# MusicalWheelchair.net
KiCad netlist of a schematic drawn in EAGLE
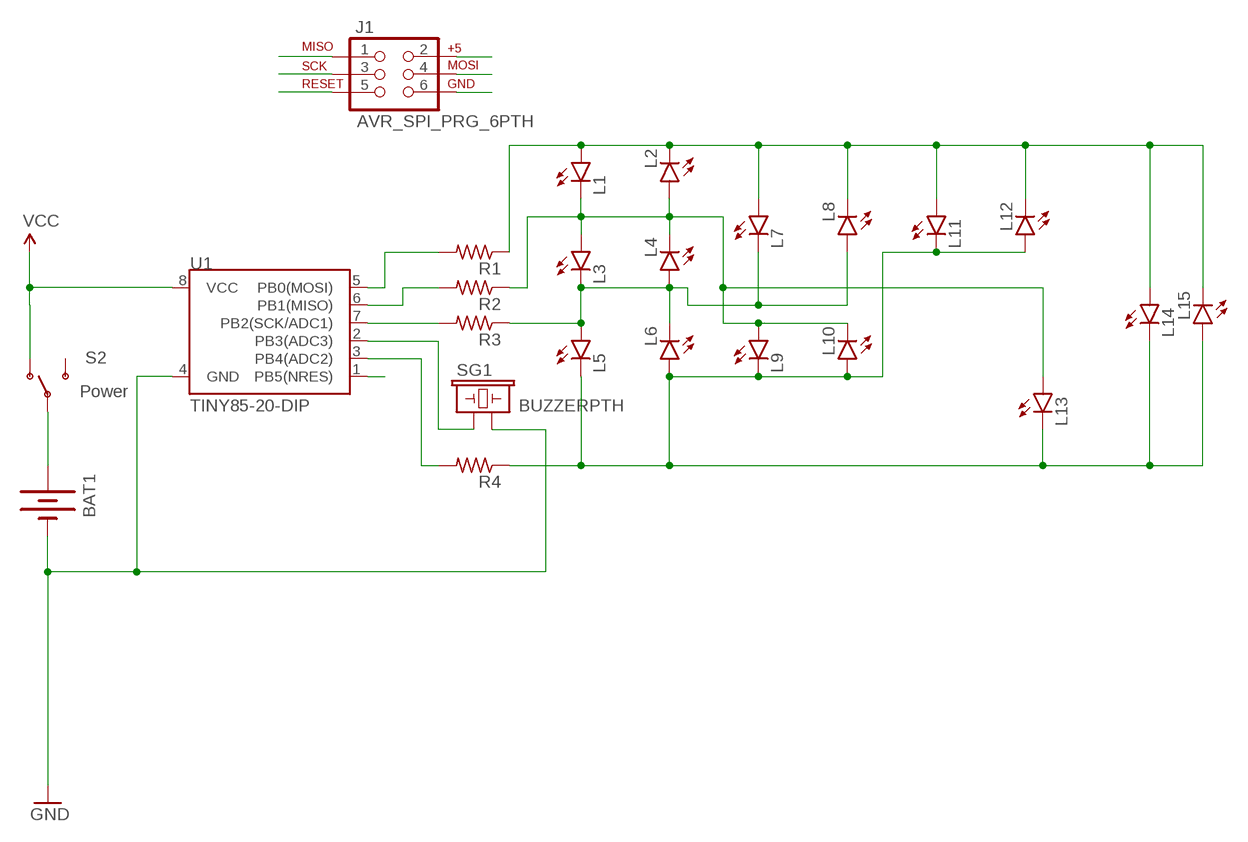
[diagram p0: schematic, sheet 1]

(export (version "E")
  (design (tool "Eeschema 10.0.6"))
  (components
    (comp (ref "BAT1")
      (value "BATTERY20PTH")
      (footprint "eagle-import:BATTCOM_20MM_PTH")
      (libsource (lib "eagle-import") (part "BATTERY20PTH"))
    )
    (comp (ref "J1")
      (value "AVR_SPI_PRG_6PTH")
      (footprint "eagle-import:2X3")
      (libsource (lib "eagle-import") (part "AVR_SPI_PRG_6PTH"))
    )
    (comp (ref "L1")
      (value "LED5MM")
      (footprint "eagle-import:LED5MM")
      (libsource (lib "eagle-import") (part "LED5MM"))
    )
    (comp (ref "L2")
      (value "LED5MM")
      (footprint "eagle-import:LED5MM")
      (libsource (lib "eagle-import") (part "LED5MM"))
    )
    (comp (ref "L3")
      (value "LED5MM")
      (footprint "eagle-import:LED5MM")
      (libsource (lib "eagle-import") (part "LED5MM"))
    )
    (comp (ref "L4")
      (value "LED5MM")
      (footprint "eagle-import:LED5MM")
      (libsource (lib "eagle-import") (part "LED5MM"))
    )
    (comp (ref "L5")
      (value "LED5MM")
      (footprint "eagle-import:LED5MM")
      (libsource (lib "eagle-import") (part "LED5MM"))
    )
    (comp (ref "L6")
      (value "LED5MM")
      (footprint "eagle-import:LED5MM")
      (libsource (lib "eagle-import") (part "LED5MM"))
    )
    (comp (ref "L7")
      (value "LED5MM")
      (footprint "eagle-import:LED5MM")
      (libsource (lib "eagle-import") (part "LED5MM"))
    )
    (comp (ref "L8")
      (value "LED5MM")
      (footprint "eagle-import:LED5MM")
      (libsource (lib "eagle-import") (part "LED5MM"))
    )
    (comp (ref "L9")
      (value "LED5MM")
      (footprint "eagle-import:LED5MM")
      (libsource (lib "eagle-import") (part "LED5MM"))
    )
    (comp (ref "L10")
      (value "LED5MM")
      (footprint "eagle-import:LED5MM")
      (libsource (lib "eagle-import") (part "LED5MM"))
    )
    (comp (ref "L11")
      (value "LED5MM")
      (footprint "eagle-import:LED5MM")
      (libsource (lib "eagle-import") (part "LED5MM"))
    )
    (comp (ref "L12")
      (value "LED5MM")
      (footprint "eagle-import:LED5MM")
      (libsource (lib "eagle-import") (part "LED5MM"))
    )
    (comp (ref "L13")
      (value "LED5MM")
      (footprint "eagle-import:LED5MM")
      (libsource (lib "eagle-import") (part "LED5MM"))
    )
    (comp (ref "L14")
      (value "LED5MM")
      (footprint "eagle-import:LED5MM")
      (libsource (lib "eagle-import") (part "LED5MM"))
    )
    (comp (ref "L15")
      (value "LED5MM")
      (footprint "eagle-import:LED5MM")
      (libsource (lib "eagle-import") (part "LED5MM"))
    )
    (comp (ref "R1")
      (value "R-US_0204/5")
      (footprint "eagle-import:0204_5")
      (libsource (lib "eagle-import") (part "R-US_0204/5"))
    )
    (comp (ref "R2")
      (value "R-US_0204/5")
      (footprint "eagle-import:0204_5")
      (libsource (lib "eagle-import") (part "R-US_0204/5"))
    )
    (comp (ref "R3")
      (value "R-US_0204/5")
      (footprint "eagle-import:0204_5")
      (libsource (lib "eagle-import") (part "R-US_0204/5"))
    )
    (comp (ref "R4")
      (value "R-US_0204/5")
      (footprint "eagle-import:0204_5")
      (libsource (lib "eagle-import") (part "R-US_0204/5"))
    )
    (comp (ref "S2")
      (value "Power")
      (footprint "eagle-import:SWITCH-SPDT")
      (libsource (lib "eagle-import") (part "SWITCH-SPDTPTH"))
    )
    (comp (ref "SG1")
      (value "BUZZERPTH")
      (footprint "eagle-import:BUZZER-12MM")
      (libsource (lib "eagle-import") (part "BUZZERPTH"))
    )
    (comp (ref "U1")
      (value "TINY85-20-DIP")
      (footprint "eagle-import:DIP08")
      (libsource (lib "eagle-import") (part "ATTINY45TINY85-20-DIP"))
    )
  )
  (nets
    (net (code "1") (name "/MISO") (class "Default")
      (node (ref "J1") (pin "1") (pinfunction "1_1") (pintype "passive"))
      (node (ref "R2") (pin "2") (pinfunction "2_2") (pintype "passive"))
      (node (ref "U1") (pin "6") (pinfunction "PB1(MISO)_6") (pintype "bidirectional"))
    )
    (net (code "2") (name "/MOSI") (class "Default")
      (node (ref "J1") (pin "4") (pinfunction "4_4") (pintype "passive"))
      (node (ref "R1") (pin "2") (pinfunction "2_2") (pintype "passive"))
      (node (ref "U1") (pin "5") (pinfunction "PB0(MOSI)_5") (pintype "bidirectional"))
    )
    (net (code "3") (name "/RST") (class "Default")
      (node (ref "J1") (pin "5") (pinfunction "5_5") (pintype "passive"))
      (node (ref "U1") (pin "1") (pinfunction "PB5(NRES)_1") (pintype "bidirectional"))
    )
    (net (code "4") (name "/SCK") (class "Default")
      (node (ref "J1") (pin "3") (pinfunction "3_3") (pintype "passive"))
      (node (ref "R3") (pin "2") (pinfunction "2_2") (pintype "passive"))
      (node (ref "U1") (pin "7") (pinfunction "PB2(SCK/ADC1)_7") (pintype "bidirectional"))
    )
    (net (code "5") (name "GND") (class "Default")
      (node (ref "BAT1") (pin "2") (pinfunction "-_2") (pintype "power_in"))
      (node (ref "J1") (pin "6") (pinfunction "6_6") (pintype "passive"))
      (node (ref "SG1") (pin "-") (pinfunction "2_-") (pintype "passive"))
      (node (ref "U1") (pin "4") (pinfunction "GND_4") (pintype "bidirectional"))
    )
    (net (code "6") (name "Net-(BAT1-+)") (class "Default")
      (node (ref "BAT1") (pin "1") (pinfunction "+_1") (pintype "power_in"))
      (node (ref "S2") (pin "2") (pinfunction "P_2") (pintype "passive"))
    )
    (net (code "7") (name "Net-(L1-C)") (class "Default")
      (node (ref "L1") (pin "K") (pinfunction "C_K") (pintype "passive"))
      (node (ref "L10") (pin "K") (pinfunction "C_K") (pintype "passive"))
      (node (ref "L13") (pin "A") (pinfunction "A_A") (pintype "passive"))
      (node (ref "L2") (pin "A") (pinfunction "A_A") (pintype "passive"))
      (node (ref "L3") (pin "A") (pinfunction "A_A") (pintype "passive"))
      (node (ref "L4") (pin "K") (pinfunction "C_K") (pintype "passive"))
      (node (ref "L9") (pin "A") (pinfunction "A_A") (pintype "passive"))
      (node (ref "R2") (pin "1") (pinfunction "1_1") (pintype "passive"))
    )
    (net (code "8") (name "Net-(L3-C)") (class "Default")
      (node (ref "L3") (pin "K") (pinfunction "C_K") (pintype "passive"))
      (node (ref "L4") (pin "A") (pinfunction "A_A") (pintype "passive"))
      (node (ref "L5") (pin "A") (pinfunction "A_A") (pintype "passive"))
      (node (ref "L6") (pin "K") (pinfunction "C_K") (pintype "passive"))
      (node (ref "L7") (pin "K") (pinfunction "C_K") (pintype "passive"))
      (node (ref "L8") (pin "A") (pinfunction "A_A") (pintype "passive"))
      (node (ref "R3") (pin "1") (pinfunction "1_1") (pintype "passive"))
    )
    (net (code "9") (name "Net-(L11-C)") (class "Default")
      (node (ref "L10") (pin "A") (pinfunction "A_A") (pintype "passive"))
      (node (ref "L11") (pin "K") (pinfunction "C_K") (pintype "passive"))
      (node (ref "L12") (pin "A") (pinfunction "A_A") (pintype "passive"))
      (node (ref "L13") (pin "K") (pinfunction "C_K") (pintype "passive"))
      (node (ref "L14") (pin "K") (pinfunction "C_K") (pintype "passive"))
      (node (ref "L15") (pin "A") (pinfunction "A_A") (pintype "passive"))
      (node (ref "L5") (pin "K") (pinfunction "C_K") (pintype "passive"))
      (node (ref "L6") (pin "A") (pinfunction "A_A") (pintype "passive"))
      (node (ref "L9") (pin "K") (pinfunction "C_K") (pintype "passive"))
      (node (ref "R4") (pin "1") (pinfunction "1_1") (pintype "passive"))
    )
    (net (code "10") (name "Net-(L12-C)") (class "Default")
      (node (ref "L1") (pin "A") (pinfunction "A_A") (pintype "passive"))
      (node (ref "L11") (pin "A") (pinfunction "A_A") (pintype "passive"))
      (node (ref "L12") (pin "K") (pinfunction "C_K") (pintype "passive"))
      (node (ref "L14") (pin "A") (pinfunction "A_A") (pintype "passive"))
      (node (ref "L15") (pin "K") (pinfunction "C_K") (pintype "passive"))
      (node (ref "L2") (pin "K") (pinfunction "C_K") (pintype "passive"))
      (node (ref "L7") (pin "A") (pinfunction "A_A") (pintype "passive"))
      (node (ref "L8") (pin "K") (pinfunction "C_K") (pintype "passive"))
      (node (ref "R1") (pin "1") (pinfunction "1_1") (pintype "passive"))
    )
    (net (code "11") (name "Net-(SG1-1)") (class "Default")
      (node (ref "SG1") (pin "+") (pinfunction "1_+") (pintype "passive"))
      (node (ref "U1") (pin "2") (pinfunction "PB3(ADC3)_2") (pintype "bidirectional"))
    )
    (net (code "12") (name "Net-(U1-PB4(ADC2))") (class "Default")
      (node (ref "R4") (pin "2") (pinfunction "2_2") (pintype "passive"))
      (node (ref "U1") (pin "3") (pinfunction "PB4(ADC2)_3") (pintype "bidirectional"))
    )
    (net (code "13") (name "VCC") (class "Default")
      (node (ref "J1") (pin "2") (pinfunction "2_2") (pintype "passive"))
      (node (ref "S2") (pin "1") (pinfunction "O_1") (pintype "passive"))
      (node (ref "U1") (pin "8") (pinfunction "VCC_8") (pintype "bidirectional"))
    )
    (net (code "14") (name "unconnected-(S2-S-Pad3)") (class "Default")
      (node (ref "S2") (pin "3") (pinfunction "S_3") (pintype "passive"))
    )
  )
)
